# Repeater.net
KiCad netlist of a schematic drawn in Altium Designer
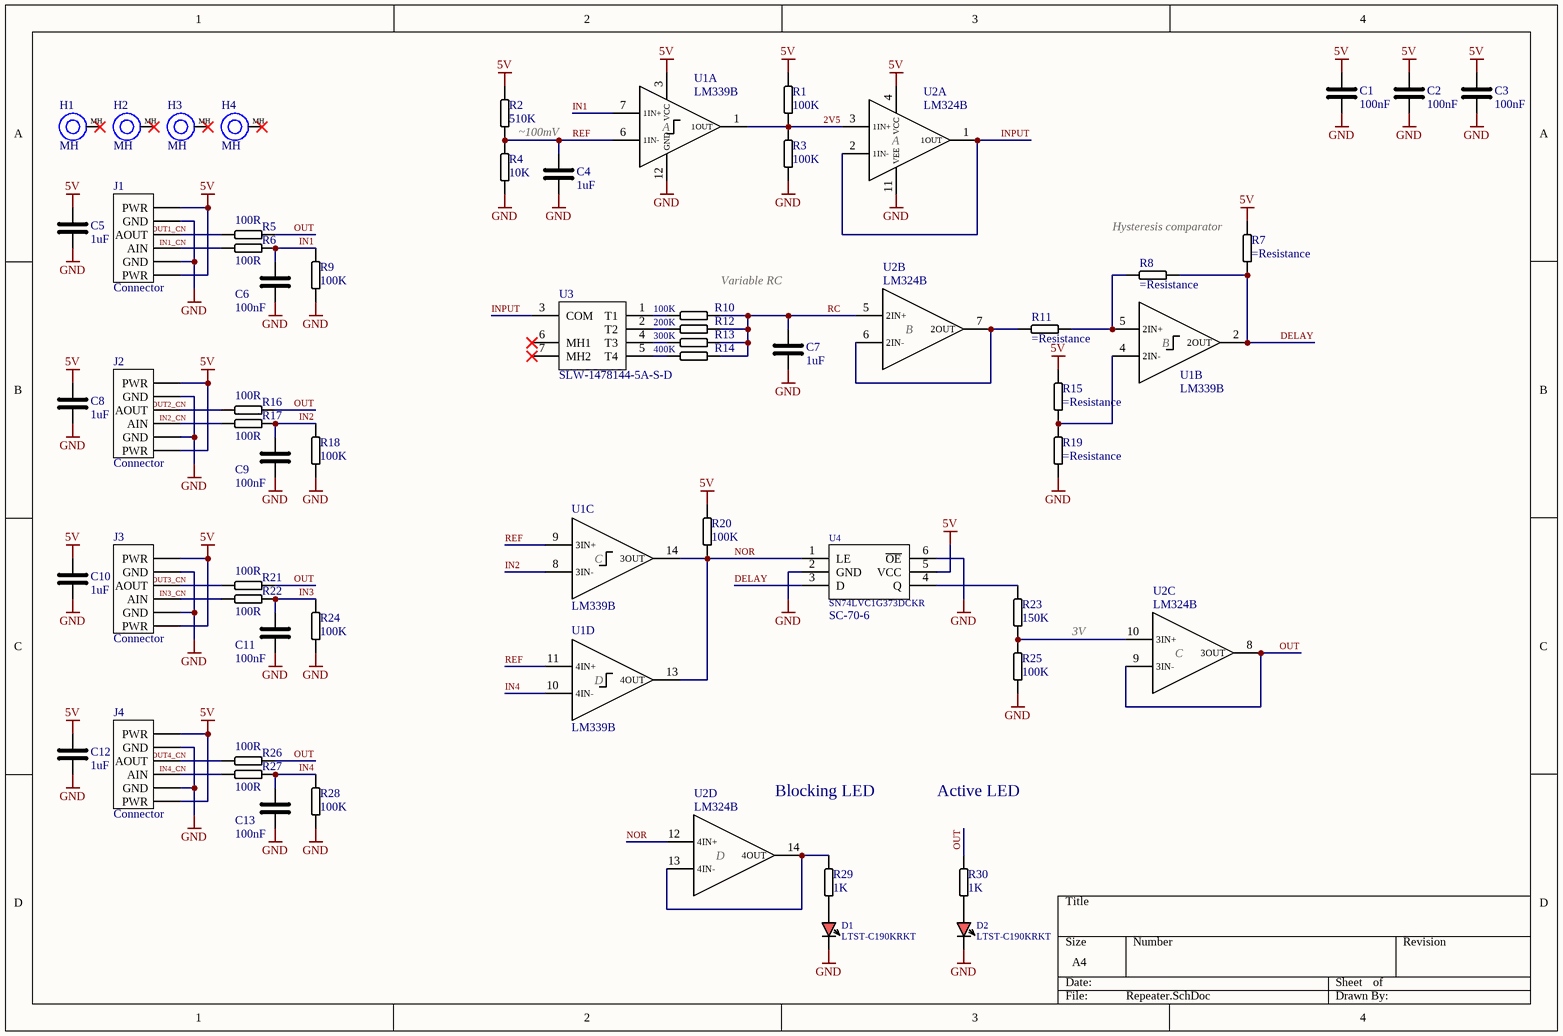
[diagram p0: Repeater.SchDoc]

(export (version "E")
  (design (tool "Eeschema 10.0.6"))
  (components
    (comp (ref "C1") (value "100nF") (footprint "CAP0603") (libsource (lib "Components") (part "Capacitor")))
    (comp (ref "C2") (value "100nF") (footprint "CAP0603") (libsource (lib "Components") (part "Capacitor")))
    (comp (ref "C3") (value "100nF") (footprint "CAP0603") (libsource (lib "Components") (part "Capacitor")))
    (comp (ref "C4") (value "1uF") (footprint "CAP0603") (libsource (lib "Components") (part "Capacitor")))
    (comp (ref "C5") (value "1uF") (footprint "CAP0603") (libsource (lib "Components") (part "Capacitor")))
    (comp (ref "C6") (value "100nF") (footprint "CAP0603") (libsource (lib "Components") (part "Capacitor")))
    (comp (ref "C7") (value "1uF") (footprint "CAP0603") (libsource (lib "Components") (part "Capacitor")))
    (comp (ref "C8") (value "1uF") (footprint "CAP0603") (libsource (lib "Components") (part "Capacitor")))
    (comp (ref "C9") (value "100nF") (footprint "CAP0603") (libsource (lib "Components") (part "Capacitor")))
    (comp (ref "C10") (value "1uF") (footprint "CAP0603") (libsource (lib "Components") (part "Capacitor")))
    (comp (ref "C11") (value "100nF") (footprint "CAP0603") (libsource (lib "Components") (part "Capacitor")))
    (comp (ref "C12") (value "1uF") (footprint "CAP0603") (libsource (lib "Components") (part "Capacitor")))
    (comp (ref "C13") (value "100nF") (footprint "CAP0603") (libsource (lib "Components") (part "Capacitor")))
    (comp (ref "D1")
      (value "LTST-C190KRKT")
      (footprint "LED0603")
      (libsource (lib "Components") (part "LTST-C190KRKT"))
    )
    (comp (ref "D2")
      (value "LTST-C190KRKT")
      (footprint "LED0603")
      (libsource (lib "Components") (part "LTST-C190KRKT"))
    )
    (comp (ref "H1")
      (value "MH")
      (footprint "MOUNTING_HOLE_M2.5")
      (libsource (lib "Components") (part "MountingHole"))
    )
    (comp (ref "H2")
      (value "MH")
      (footprint "MOUNTING_HOLE_M2.5")
      (libsource (lib "Components") (part "MountingHole"))
    )
    (comp (ref "H3")
      (value "MH")
      (footprint "MOUNTING_HOLE_M2.5")
      (libsource (lib "Components") (part "MountingHole"))
    )
    (comp (ref "H4")
      (value "MH")
      (footprint "MOUNTING_HOLE_M2.5")
      (libsource (lib "Components") (part "MountingHole"))
    )
    (comp (ref "J1")
      (value "Connector")
      (footprint "CONNECTOR")
      (libsource (lib "Components") (part "Connector"))
    )
    (comp (ref "J2")
      (value "Connector")
      (footprint "CONNECTOR")
      (libsource (lib "Components") (part "Connector"))
    )
    (comp (ref "J3")
      (value "Connector")
      (footprint "CONNECTOR")
      (libsource (lib "Components") (part "Connector"))
    )
    (comp (ref "J4")
      (value "Connector")
      (footprint "CONNECTOR")
      (libsource (lib "Components") (part "Connector"))
    )
    (comp (ref "R1") (value "100K") (footprint "RES0603") (libsource (lib "Components") (part "Resistor")))
    (comp (ref "R2") (value "510K") (footprint "RES0603") (libsource (lib "Components") (part "Resistor")))
    (comp (ref "R3") (value "100K") (footprint "RES0603") (libsource (lib "Components") (part "Resistor")))
    (comp (ref "R4") (value "10K") (footprint "RES0603") (libsource (lib "Components") (part "Resistor")))
    (comp (ref "R5") (value "100R") (footprint "RES0603") (libsource (lib "Components") (part "Resistor")))
    (comp (ref "R6") (value "100R") (footprint "RES0603") (libsource (lib "Components") (part "Resistor")))
    (comp (ref "R7") (value "~") (footprint "RES0603") (libsource (lib "Components") (part "Resistor")))
    (comp (ref "R8") (value "~") (footprint "RES0603") (libsource (lib "Components") (part "Resistor")))
    (comp (ref "R9") (value "100K") (footprint "RES0603") (libsource (lib "Components") (part "Resistor")))
    (comp (ref "R10") (value "100K") (footprint "RES0603") (libsource (lib "Components") (part "Resistor")))
    (comp (ref "R11") (value "~") (footprint "RES0603") (libsource (lib "Components") (part "Resistor")))
    (comp (ref "R12") (value "200K") (footprint "RES0603") (libsource (lib "Components") (part "Resistor")))
    (comp (ref "R13") (value "300K") (footprint "RES0603") (libsource (lib "Components") (part "Resistor")))
    (comp (ref "R14") (value "400K") (footprint "RES0603") (libsource (lib "Components") (part "Resistor")))
    (comp (ref "R15") (value "~") (footprint "RES0603") (libsource (lib "Components") (part "Resistor")))
    (comp (ref "R16") (value "100R") (footprint "RES0603") (libsource (lib "Components") (part "Resistor")))
    (comp (ref "R17") (value "100R") (footprint "RES0603") (libsource (lib "Components") (part "Resistor")))
    (comp (ref "R18") (value "100K") (footprint "RES0603") (libsource (lib "Components") (part "Resistor")))
    (comp (ref "R19") (value "~") (footprint "RES0603") (libsource (lib "Components") (part "Resistor")))
    (comp (ref "R20") (value "100K") (footprint "RES0603") (libsource (lib "Components") (part "Resistor")))
    (comp (ref "R21") (value "100R") (footprint "RES0603") (libsource (lib "Components") (part "Resistor")))
    (comp (ref "R22") (value "100R") (footprint "RES0603") (libsource (lib "Components") (part "Resistor")))
    (comp (ref "R23") (value "150K") (footprint "RES0603") (libsource (lib "Components") (part "Resistor")))
    (comp (ref "R24") (value "100K") (footprint "RES0603") (libsource (lib "Components") (part "Resistor")))
    (comp (ref "R25") (value "100K") (footprint "RES0603") (libsource (lib "Components") (part "Resistor")))
    (comp (ref "R26") (value "100R") (footprint "RES0603") (libsource (lib "Components") (part "Resistor")))
    (comp (ref "R27") (value "100R") (footprint "RES0603") (libsource (lib "Components") (part "Resistor")))
    (comp (ref "R28") (value "100K") (footprint "RES0603") (libsource (lib "Components") (part "Resistor")))
    (comp (ref "R29") (value "1K") (footprint "RES0603") (libsource (lib "Components") (part "Resistor")))
    (comp (ref "R30") (value "1K") (footprint "RES0603") (libsource (lib "Components") (part "Resistor")))
    (comp (ref "U1")
      (value "LM339B")
      (footprint "TSSOP_16P")
      (libsource (lib "Components") (part "LM339BIPWR"))
    )
    (comp (ref "U2")
      (value "LM324B")
      (footprint "TSSOP_14P")
      (libsource (lib "Components") (part "LM324BIPWR"))
    )
    (comp (ref "U3")
      (value "SLW-1478144-5A-S-D")
      (footprint "SOT-363-6")
      (libsource (lib "Components") (part "SLW-1478144-5A-S-D"))
    )
    (comp (ref "U4")
      (value "SN74LVC1G373DCKR")
      (footprint "SOT-363-6")
      (fields (field (name "PACKAGE") "SC-70-6") (field (name "MANUFACTURER") "TI"))
      (libsource (lib "evomeas_database") (part "SN74LVC1G373"))
    )
  )
  (nets
    (net (code "1") (name "/2V5") (class "Default")
      (node (ref "R1") (pin "2") (pinfunction "2_2") (pintype "passive"))
      (node (ref "R3") (pin "1") (pinfunction "1_1") (pintype "passive"))
      (node (ref "U1") (pin "1") (pinfunction "1OUT_1") (pintype "passive"))
      (node (ref "U2") (pin "3") (pinfunction "1IN+_3") (pintype "passive"))
    )
    (net (code "2") (name "/DELAY") (class "Default")
      (node (ref "R7") (pin "1") (pinfunction "1_1") (pintype "passive"))
      (node (ref "R8") (pin "1") (pinfunction "1_1") (pintype "passive"))
      (node (ref "U1") (pin "2") (pinfunction "2OUT_2") (pintype "passive"))
      (node (ref "U4") (pin "3") (pinfunction "D_3") (pintype "passive"))
    )
    (net (code "3") (name "/IN1") (class "Default")
      (node (ref "C6") (pin "1") (pinfunction "1_1") (pintype "passive"))
      (node (ref "R6") (pin "2") (pinfunction "2_2") (pintype "passive"))
      (node (ref "R9") (pin "1") (pinfunction "1_1") (pintype "passive"))
      (node (ref "U1") (pin "7") (pinfunction "1IN+_7") (pintype "passive"))
    )
    (net (code "4") (name "/IN1_CN") (class "Default")
      (node (ref "J1") (pin "3") (pinfunction "AIN_3") (pintype "passive"))
      (node (ref "R6") (pin "1") (pinfunction "1_1") (pintype "passive"))
    )
    (net (code "5") (name "/IN2") (class "Default")
      (node (ref "C9") (pin "1") (pinfunction "1_1") (pintype "passive"))
      (node (ref "R17") (pin "2") (pinfunction "2_2") (pintype "passive"))
      (node (ref "R18") (pin "1") (pinfunction "1_1") (pintype "passive"))
      (node (ref "U1") (pin "8") (pinfunction "3IN-_8") (pintype "passive"))
    )
    (net (code "6") (name "/IN2_CN") (class "Default")
      (node (ref "J2") (pin "3") (pinfunction "AIN_3") (pintype "passive"))
      (node (ref "R17") (pin "1") (pinfunction "1_1") (pintype "passive"))
    )
    (net (code "7") (name "/IN3") (class "Default")
      (node (ref "C11") (pin "1") (pinfunction "1_1") (pintype "passive"))
      (node (ref "R22") (pin "2") (pinfunction "2_2") (pintype "passive"))
      (node (ref "R24") (pin "1") (pinfunction "1_1") (pintype "passive"))
    )
    (net (code "8") (name "/IN3_CN") (class "Default")
      (node (ref "J3") (pin "3") (pinfunction "AIN_3") (pintype "passive"))
      (node (ref "R22") (pin "1") (pinfunction "1_1") (pintype "passive"))
    )
    (net (code "9") (name "/IN4") (class "Default")
      (node (ref "C13") (pin "1") (pinfunction "1_1") (pintype "passive"))
      (node (ref "R27") (pin "2") (pinfunction "2_2") (pintype "passive"))
      (node (ref "R28") (pin "1") (pinfunction "1_1") (pintype "passive"))
      (node (ref "U1") (pin "10") (pinfunction "4IN-_10") (pintype "passive"))
    )
    (net (code "10") (name "/IN4_CN") (class "Default")
      (node (ref "J4") (pin "3") (pinfunction "AIN_3") (pintype "passive"))
      (node (ref "R27") (pin "1") (pinfunction "1_1") (pintype "passive"))
    )
    (net (code "11") (name "/INPUT") (class "Default")
      (node (ref "U2") (pin "1") (pinfunction "1OUT_1") (pintype "passive"))
      (node (ref "U2") (pin "2") (pinfunction "1IN-_2") (pintype "passive"))
      (node (ref "U3") (pin "3") (pinfunction "COM_3") (pintype "passive"))
    )
    (net (code "12") (name "/NOR") (class "Default")
      (node (ref "R20") (pin "1") (pinfunction "1_1") (pintype "passive"))
      (node (ref "U1") (pin "13") (pinfunction "4OUT_13") (pintype "passive"))
      (node (ref "U1") (pin "14") (pinfunction "3OUT_14") (pintype "passive"))
      (node (ref "U2") (pin "12") (pinfunction "4IN+_12") (pintype "passive"))
      (node (ref "U4") (pin "1") (pinfunction "LE_1") (pintype "passive"))
    )
    (net (code "13") (name "/OUT") (class "Default")
      (node (ref "R16") (pin "2") (pinfunction "2_2") (pintype "passive"))
      (node (ref "R21") (pin "2") (pinfunction "2_2") (pintype "passive"))
      (node (ref "R26") (pin "2") (pinfunction "2_2") (pintype "passive"))
      (node (ref "R30") (pin "2") (pinfunction "2_2") (pintype "passive"))
      (node (ref "R5") (pin "2") (pinfunction "2_2") (pintype "passive"))
      (node (ref "U2") (pin "8") (pinfunction "3OUT_8") (pintype "passive"))
      (node (ref "U2") (pin "9") (pinfunction "3IN-_9") (pintype "passive"))
    )
    (net (code "14") (name "/OUT1_CN") (class "Default")
      (node (ref "J1") (pin "4") (pinfunction "AOUT_4") (pintype "passive"))
      (node (ref "R5") (pin "1") (pinfunction "1_1") (pintype "passive"))
    )
    (net (code "15") (name "/OUT2_CN") (class "Default")
      (node (ref "J2") (pin "4") (pinfunction "AOUT_4") (pintype "passive"))
      (node (ref "R16") (pin "1") (pinfunction "1_1") (pintype "passive"))
    )
    (net (code "16") (name "/OUT3_CN") (class "Default")
      (node (ref "J3") (pin "4") (pinfunction "AOUT_4") (pintype "passive"))
      (node (ref "R21") (pin "1") (pinfunction "1_1") (pintype "passive"))
    )
    (net (code "17") (name "/OUT4_CN") (class "Default")
      (node (ref "J4") (pin "4") (pinfunction "AOUT_4") (pintype "passive"))
      (node (ref "R26") (pin "1") (pinfunction "1_1") (pintype "passive"))
    )
    (net (code "18") (name "/RC") (class "Default")
      (node (ref "C7") (pin "1") (pinfunction "1_1") (pintype "passive"))
      (node (ref "R10") (pin "2") (pinfunction "2_2") (pintype "passive"))
      (node (ref "R12") (pin "2") (pinfunction "2_2") (pintype "passive"))
      (node (ref "R13") (pin "2") (pinfunction "2_2") (pintype "passive"))
      (node (ref "R14") (pin "2") (pinfunction "2_2") (pintype "passive"))
      (node (ref "U2") (pin "5") (pinfunction "2IN+_5") (pintype "passive"))
    )
    (net (code "19") (name "/REF") (class "Default")
      (node (ref "C4") (pin "1") (pinfunction "1_1") (pintype "passive"))
      (node (ref "R2") (pin "1") (pinfunction "1_1") (pintype "passive"))
      (node (ref "R4") (pin "2") (pinfunction "2_2") (pintype "passive"))
      (node (ref "U1") (pin "11") (pinfunction "4IN+_11") (pintype "passive"))
      (node (ref "U1") (pin "6") (pinfunction "1IN-_6") (pintype "passive"))
      (node (ref "U1") (pin "9") (pinfunction "3IN+_9") (pintype "passive"))
    )
    (net (code "20") (name "5V") (class "Default")
      (node (ref "C1") (pin "1") (pinfunction "1_1") (pintype "passive"))
      (node (ref "C10") (pin "1") (pinfunction "1_1") (pintype "passive"))
      (node (ref "C12") (pin "1") (pinfunction "1_1") (pintype "passive"))
      (node (ref "C2") (pin "1") (pinfunction "1_1") (pintype "passive"))
      (node (ref "C3") (pin "1") (pinfunction "1_1") (pintype "passive"))
      (node (ref "C5") (pin "1") (pinfunction "1_1") (pintype "passive"))
      (node (ref "C8") (pin "1") (pinfunction "1_1") (pintype "passive"))
      (node (ref "J1") (pin "1") (pinfunction "PWR_1") (pintype "passive"))
      (node (ref "J1") (pin "6") (pinfunction "PWR_6") (pintype "passive"))
      (node (ref "J2") (pin "1") (pinfunction "PWR_1") (pintype "passive"))
      (node (ref "J2") (pin "6") (pinfunction "PWR_6") (pintype "passive"))
      (node (ref "J3") (pin "1") (pinfunction "PWR_1") (pintype "passive"))
      (node (ref "J3") (pin "6") (pinfunction "PWR_6") (pintype "passive"))
      (node (ref "J4") (pin "1") (pinfunction "PWR_1") (pintype "passive"))
      (node (ref "J4") (pin "6") (pinfunction "PWR_6") (pintype "passive"))
      (node (ref "R1") (pin "1") (pinfunction "1_1") (pintype "passive"))
      (node (ref "R15") (pin "2") (pinfunction "2_2") (pintype "passive"))
      (node (ref "R2") (pin "2") (pinfunction "2_2") (pintype "passive"))
      (node (ref "R20") (pin "2") (pinfunction "2_2") (pintype "passive"))
      (node (ref "R7") (pin "2") (pinfunction "2_2") (pintype "passive"))
      (node (ref "U1") (pin "3") (pinfunction "VCC_3") (pintype "passive"))
      (node (ref "U2") (pin "4") (pinfunction "VCC_4") (pintype "passive"))
      (node (ref "U4") (pin "5") (pinfunction "VCC_5") (pintype "passive"))
    )
    (net (code "21") (name "GND") (class "Default")
      (node (ref "C1") (pin "2") (pinfunction "2_2") (pintype "passive"))
      (node (ref "C10") (pin "2") (pinfunction "2_2") (pintype "passive"))
      (node (ref "C11") (pin "2") (pinfunction "2_2") (pintype "passive"))
      (node (ref "C12") (pin "2") (pinfunction "2_2") (pintype "passive"))
      (node (ref "C13") (pin "2") (pinfunction "2_2") (pintype "passive"))
      (node (ref "C2") (pin "2") (pinfunction "2_2") (pintype "passive"))
      (node (ref "C3") (pin "2") (pinfunction "2_2") (pintype "passive"))
      (node (ref "C4") (pin "2") (pinfunction "2_2") (pintype "passive"))
      (node (ref "C5") (pin "2") (pinfunction "2_2") (pintype "passive"))
      (node (ref "C6") (pin "2") (pinfunction "2_2") (pintype "passive"))
      (node (ref "C7") (pin "2") (pinfunction "2_2") (pintype "passive"))
      (node (ref "C8") (pin "2") (pinfunction "2_2") (pintype "passive"))
      (node (ref "C9") (pin "2") (pinfunction "2_2") (pintype "passive"))
      (node (ref "D1") (pin "C") (pinfunction "C_C") (pintype "passive"))
      (node (ref "D2") (pin "C") (pinfunction "C_C") (pintype "passive"))
      (node (ref "J1") (pin "2") (pinfunction "GND_2") (pintype "passive"))
      (node (ref "J1") (pin "5") (pinfunction "GND_5") (pintype "passive"))
      (node (ref "J2") (pin "2") (pinfunction "GND_2") (pintype "passive"))
      (node (ref "J2") (pin "5") (pinfunction "GND_5") (pintype "passive"))
      (node (ref "J3") (pin "2") (pinfunction "GND_2") (pintype "passive"))
      (node (ref "J3") (pin "5") (pinfunction "GND_5") (pintype "passive"))
      (node (ref "J4") (pin "2") (pinfunction "GND_2") (pintype "passive"))
      (node (ref "J4") (pin "5") (pinfunction "GND_5") (pintype "passive"))
      (node (ref "R18") (pin "2") (pinfunction "2_2") (pintype "passive"))
      (node (ref "R19") (pin "1") (pinfunction "1_1") (pintype "passive"))
      (node (ref "R24") (pin "2") (pinfunction "2_2") (pintype "passive"))
      (node (ref "R25") (pin "1") (pinfunction "1_1") (pintype "passive"))
      (node (ref "R28") (pin "2") (pinfunction "2_2") (pintype "passive"))
      (node (ref "R3") (pin "2") (pinfunction "2_2") (pintype "passive"))
      (node (ref "R4") (pin "1") (pinfunction "1_1") (pintype "passive"))
      (node (ref "R9") (pin "2") (pinfunction "2_2") (pintype "passive"))
      (node (ref "U1") (pin "12") (pinfunction "GND_12") (pintype "passive"))
      (node (ref "U2") (pin "11") (pinfunction "VEE_11") (pintype "passive"))
      (node (ref "U4") (pin "2") (pinfunction "GND_2") (pintype "passive"))
      (node (ref "U4") (pin "6") (pinfunction "~{OE}_6") (pintype "passive"))
    )
    (net (code "22") (name "Net-(D1-PadA)") (class "Default")
      (node (ref "D1") (pin "A") (pinfunction "A_A") (pintype "passive"))
      (node (ref "R29") (pin "1") (pinfunction "1_1") (pintype "passive"))
    )
    (net (code "23") (name "Net-(D2-PadA)") (class "Default")
      (node (ref "D2") (pin "A") (pinfunction "A_A") (pintype "passive"))
      (node (ref "R30") (pin "1") (pinfunction "1_1") (pintype "passive"))
    )
    (net (code "24") (name "Net-(U1B-2IN+)") (class "Default")
      (node (ref "R11") (pin "1") (pinfunction "1_1") (pintype "passive"))
      (node (ref "R8") (pin "2") (pinfunction "2_2") (pintype "passive"))
      (node (ref "U1") (pin "5") (pinfunction "2IN+_5") (pintype "passive"))
    )
    (net (code "25") (name "Net-(U1B-2IN-)") (class "Default")
      (node (ref "R15") (pin "1") (pinfunction "1_1") (pintype "passive"))
      (node (ref "R19") (pin "2") (pinfunction "2_2") (pintype "passive"))
      (node (ref "U1") (pin "4") (pinfunction "2IN-_4") (pintype "passive"))
    )
    (net (code "26") (name "Net-(U2B-2IN-)") (class "Default")
      (node (ref "R11") (pin "2") (pinfunction "2_2") (pintype "passive"))
      (node (ref "U2") (pin "6") (pinfunction "2IN-_6") (pintype "passive"))
      (node (ref "U2") (pin "7") (pinfunction "2OUT_7") (pintype "passive"))
    )
    (net (code "27") (name "Net-(U2C-3IN+)") (class "Default")
      (node (ref "R23") (pin "2") (pinfunction "2_2") (pintype "passive"))
      (node (ref "R25") (pin "2") (pinfunction "2_2") (pintype "passive"))
      (node (ref "U2") (pin "10") (pinfunction "3IN+_10") (pintype "passive"))
    )
    (net (code "28") (name "Net-(U2D-4IN-)") (class "Default")
      (node (ref "R29") (pin "2") (pinfunction "2_2") (pintype "passive"))
      (node (ref "U2") (pin "13") (pinfunction "4IN-_13") (pintype "passive"))
      (node (ref "U2") (pin "14") (pinfunction "4OUT_14") (pintype "passive"))
    )
    (net (code "29") (name "Net-(U3-T1)") (class "Default")
      (node (ref "R10") (pin "1") (pinfunction "1_1") (pintype "passive"))
      (node (ref "U3") (pin "1") (pinfunction "T1_1") (pintype "passive"))
    )
    (net (code "30") (name "Net-(U3-T2)") (class "Default")
      (node (ref "R12") (pin "1") (pinfunction "1_1") (pintype "passive"))
      (node (ref "U3") (pin "2") (pinfunction "T2_2") (pintype "passive"))
    )
    (net (code "31") (name "Net-(U3-T3)") (class "Default")
      (node (ref "R13") (pin "1") (pinfunction "1_1") (pintype "passive"))
      (node (ref "U3") (pin "4") (pinfunction "T3_4") (pintype "passive"))
    )
    (net (code "32") (name "Net-(U3-T4)") (class "Default")
      (node (ref "R14") (pin "1") (pinfunction "1_1") (pintype "passive"))
      (node (ref "U3") (pin "5") (pinfunction "T4_5") (pintype "passive"))
    )
    (net (code "33") (name "Net-(U4-Q)") (class "Default")
      (node (ref "R23") (pin "1") (pinfunction "1_1") (pintype "passive"))
      (node (ref "U4") (pin "4") (pinfunction "Q_4") (pintype "passive"))
    )
    (net (code "34") (name "unconnected-(H1-PadMH)") (class "Default")
      (node (ref "H1") (pin "MH") (pintype "passive+no_connect"))
    )
    (net (code "35") (name "unconnected-(H2-PadMH)") (class "Default")
      (node (ref "H2") (pin "MH") (pintype "passive+no_connect"))
    )
    (net (code "36") (name "unconnected-(H3-PadMH)") (class "Default")
      (node (ref "H3") (pin "MH") (pintype "passive+no_connect"))
    )
    (net (code "37") (name "unconnected-(H4-PadMH)") (class "Default")
      (node (ref "H4") (pin "MH") (pintype "passive+no_connect"))
    )
    (net (code "38") (name "unconnected-(U3-MH1-Pad6)") (class "Default")
      (node (ref "U3") (pin "6") (pinfunction "MH1_6") (pintype "passive+no_connect"))
    )
    (net (code "39") (name "unconnected-(U3-MH2-Pad7)") (class "Default")
      (node (ref "U3") (pin "7") (pinfunction "MH2_7") (pintype "passive+no_connect"))
    )
  )
)
